# SCH_DONGHO.net
KiCad netlist of a schematic drawn in Altium Designer
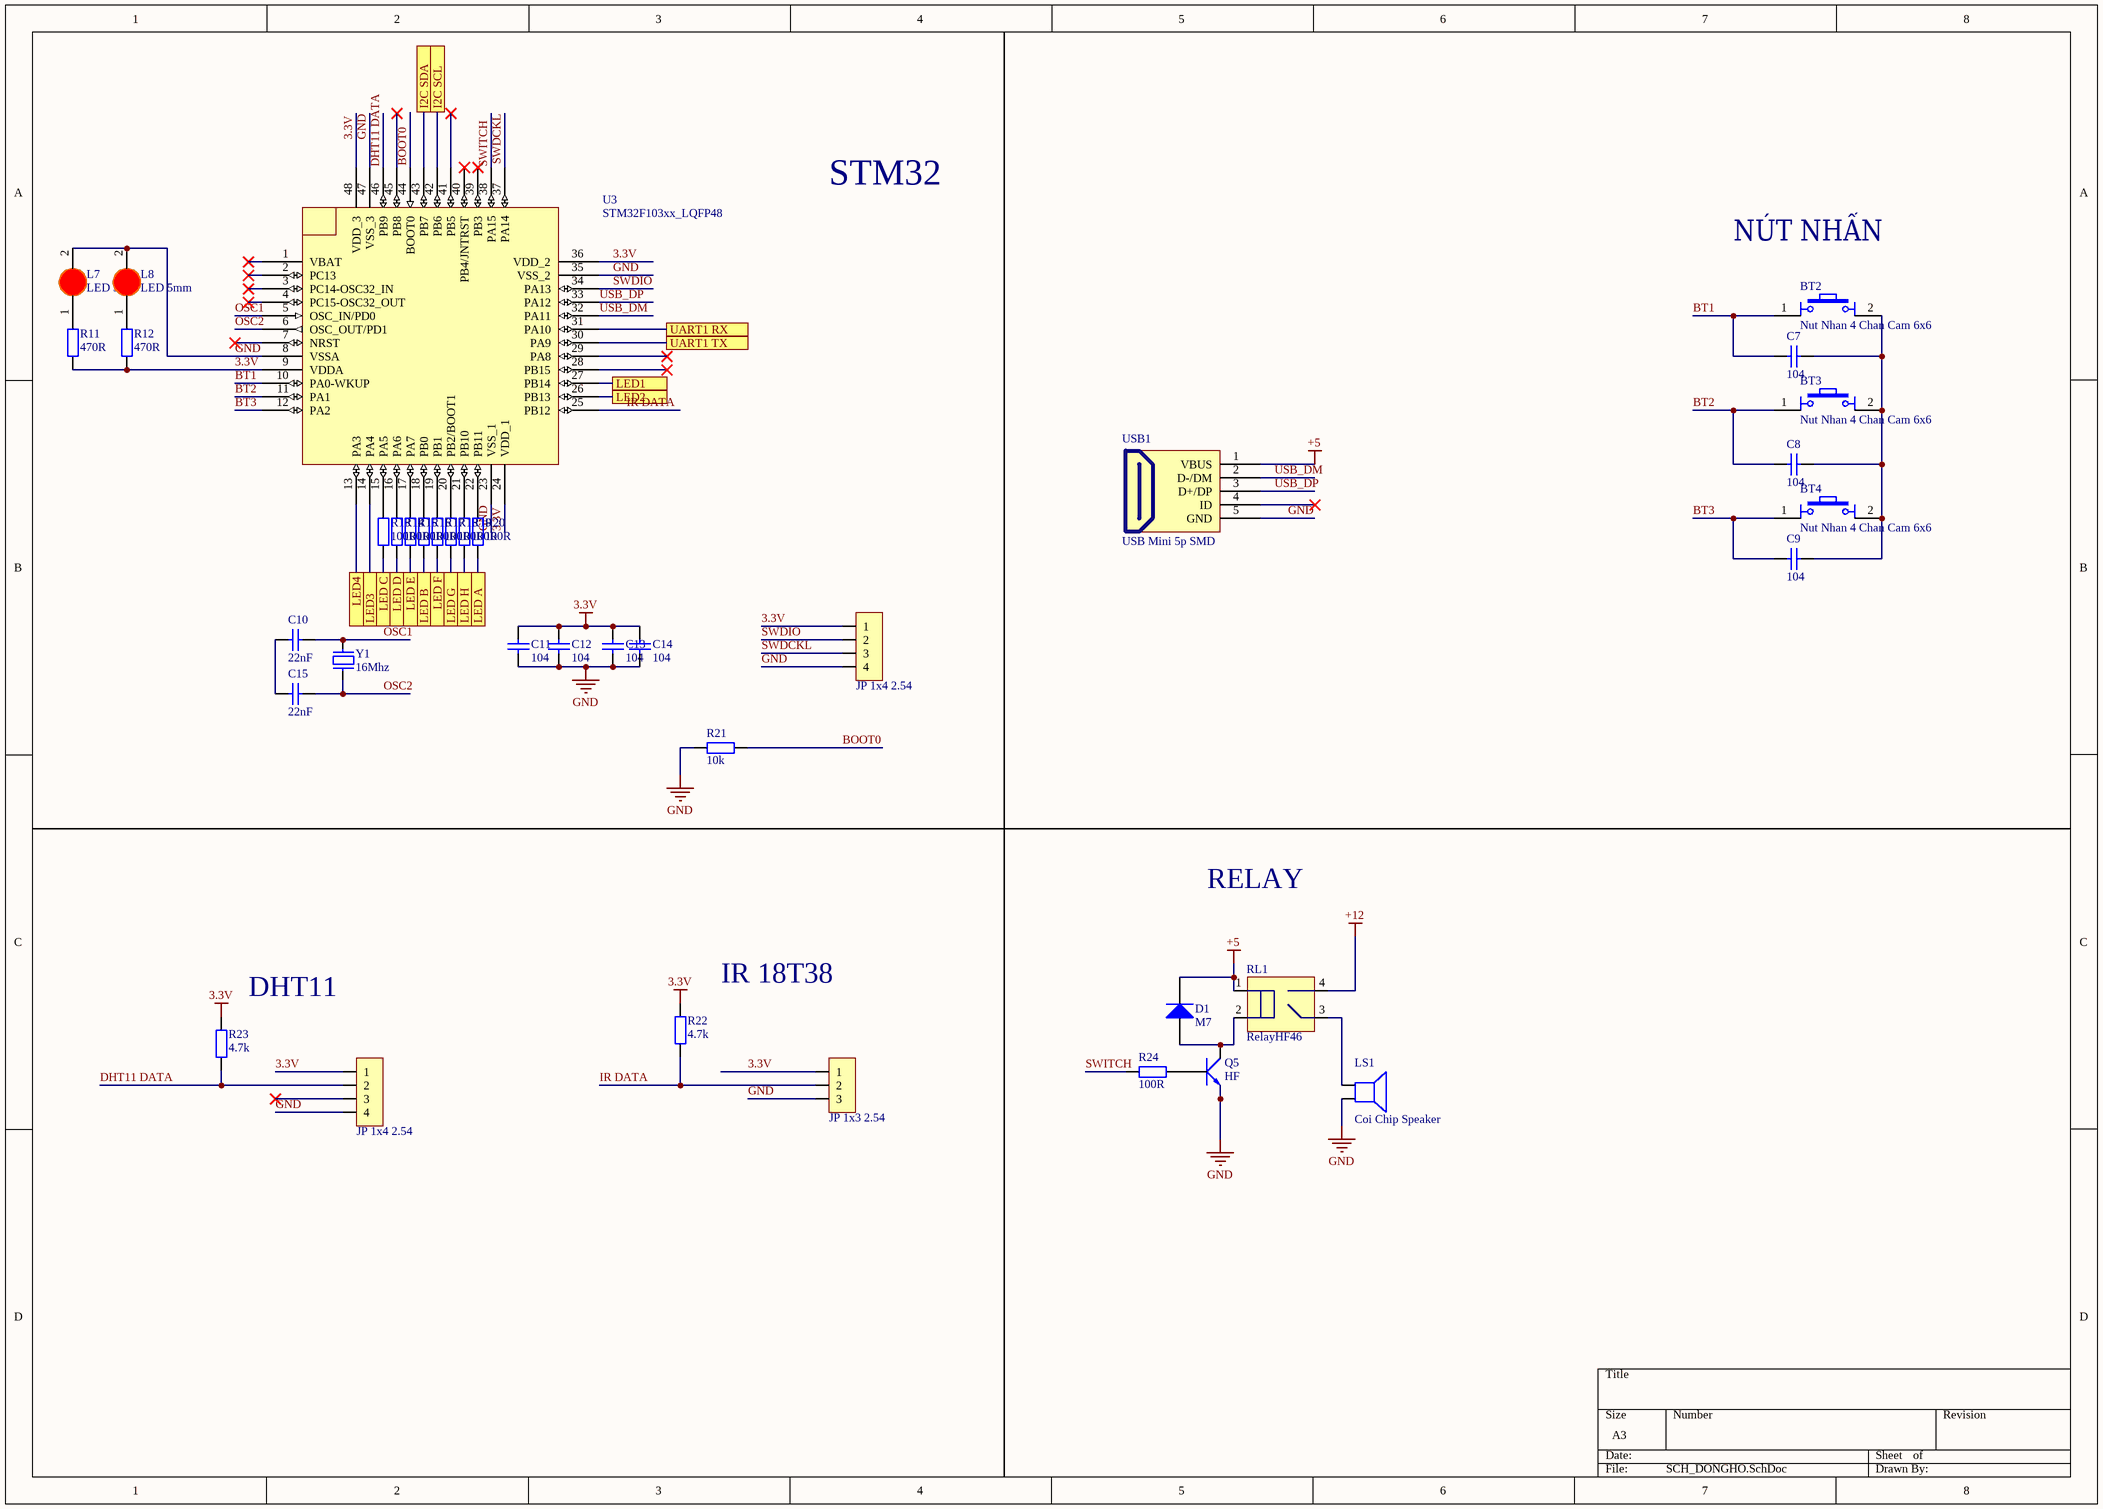
[diagram p0: SCH_DONGHO.SchDoc]

(export (version "E")
  (design (tool "Eeschema 10.0.6"))
  (components
    (comp (ref "BT2")
      (value "Nut Nhan 4 Chan Cam 6x6")
      (footprint "Nut Nhan 4 Chan Cam 6x6")
      (description "Nut Nhan 4 Chan 6x6mm")
      (libsource (lib "Altium_Lib_by_KhueNguyenCreator") (part "Nut Nhan 4 Chan Cam 6x6"))
    )
    (comp (ref "BT3")
      (value "Nut Nhan 4 Chan Cam 6x6")
      (footprint "Nut Nhan 4 Chan Cam 6x6")
      (description "Nut Nhan 4 Chan 6x6mm")
      (libsource (lib "Altium_Lib_by_KhueNguyenCreator") (part "Nut Nhan 4 Chan Cam 6x6"))
    )
    (comp (ref "BT4")
      (value "Nut Nhan 4 Chan Cam 6x6")
      (footprint "Nut Nhan 4 Chan Cam 6x6")
      (description "Nut Nhan 4 Chan 6x6mm")
      (libsource (lib "Altium_Lib_by_KhueNguyenCreator") (part "Nut Nhan 4 Chan Cam 6x6"))
    )
    (comp (ref "C7")
      (value "104")
      (footprint "tu 0805")
      (description "Dán")
      (libsource (lib "Altium_Lib_by_KhueNguyenCreator") (part "Tu 0805 104 50V 10%"))
    )
    (comp (ref "C8")
      (value "104")
      (footprint "tu 0805")
      (description "Dán")
      (libsource (lib "Altium_Lib_by_KhueNguyenCreator") (part "Tu 0805 104 50V 10%"))
    )
    (comp (ref "C9")
      (value "104")
      (footprint "tu 0805")
      (description "Dán")
      (libsource (lib "Altium_Lib_by_KhueNguyenCreator") (part "Tu 0805 104 50V 10%"))
    )
    (comp (ref "C10")
      (value "22nF")
      (footprint "tu 0805")
      (description "Dán")
      (libsource (lib "Altium_Lib_by_KhueNguyenCreator") (part "Tu 0805 22nF 50V 20%"))
    )
    (comp (ref "C11")
      (value "104")
      (footprint "tu 0805")
      (description "Dán")
      (libsource (lib "Altium_Lib_by_KhueNguyenCreator") (part "Tu 0805 104 50V 10%"))
    )
    (comp (ref "C12")
      (value "104")
      (footprint "tu 0805")
      (description "Dán")
      (libsource (lib "Altium_Lib_by_KhueNguyenCreator") (part "Tu 0805 104 50V 10%"))
    )
    (comp (ref "C13")
      (value "104")
      (footprint "tu 0805")
      (description "Dán")
      (libsource (lib "Altium_Lib_by_KhueNguyenCreator") (part "Tu 0805 104 50V 10%"))
    )
    (comp (ref "C14")
      (value "104")
      (footprint "tu 0805")
      (description "Dán")
      (libsource (lib "Altium_Lib_by_KhueNguyenCreator") (part "Tu 0805 104 50V 10%"))
    )
    (comp (ref "C15")
      (value "22nF")
      (footprint "tu 0805")
      (description "Dán")
      (libsource (lib "Altium_Lib_by_KhueNguyenCreator") (part "Tu 0805 22nF 50V 20%"))
    )
    (comp (ref "D1")
      (value "M7")
      (footprint "DIODE SMA")
      (description "Dán")
      (libsource (lib "Altium_Lib_by_KhueNguyenCreator") (part "Diode M7 ( 4007 )"))
    )
    (comp (ref "JP1")
      (value "JP 1x4 2.54")
      (footprint "JP 1x4 CT")
      (description "Cắm")
      (libsource (lib "Altium_Lib_by_KhueNguyenCreator") (part "JP 1x4 2.54 Cai Thang"))
    )
    (comp (ref "JP2")
      (value "JP 1x4 2.54")
      (footprint "JP 1x4 CT")
      (description "Cắm")
      (libsource (lib "Altium_Lib_by_KhueNguyenCreator") (part "JP 1x4 2.54 Cai Thang"))
    )
    (comp (ref "JP3")
      (value "JP 1x3 2.54")
      (footprint "JP 1x3 CT")
      (description "Cắm")
      (libsource (lib "Altium_Lib_by_KhueNguyenCreator") (part "JP 1x3 2.54 Cai Thang"))
    )
    (comp (ref "L7")
      (value "LED 5mm")
      (footprint "LED-5MM-RED")
      (description "Cắm")
      (libsource (lib "Altium_Lib_by_KhueNguyenCreator") (part "LED 5mm Do"))
    )
    (comp (ref "L8")
      (value "LED 5mm")
      (footprint "LED-5MM-RED")
      (description "Cắm")
      (libsource (lib "Altium_Lib_by_KhueNguyenCreator") (part "LED 5mm Do"))
    )
    (comp (ref "LS1")
      (value "Coi Chip Speaker")
      (footprint "Coi Chip Speacker")
      (description "Còi chip")
      (libsource (lib "Altium_Lib_by_KhueNguyenCreator") (part "Coi Chip Speaker"))
    )
    (comp (ref "Q5")
      (value "HF")
      (footprint "SOT23")
      (description "NPN transistor")
      (libsource (lib "Altium_Lib_by_KhueNguyenCreator") (part "C1815 HF SMD"))
    )
    (comp (ref "R11")
      (value "470R")
      (footprint "Tro SMD 0805")
      (description "Dán")
      (libsource (lib "Altium_Lib_by_KhueNguyenCreator") (part "Tro 0805 5% 470R"))
    )
    (comp (ref "R12")
      (value "470R")
      (footprint "Tro SMD 0805")
      (description "Dán")
      (libsource (lib "Altium_Lib_by_KhueNguyenCreator") (part "Tro 0805 5% 470R"))
    )
    (comp (ref "R13")
      (value "100R")
      (footprint "tro smd 0805")
      (description "Dán")
      (libsource (lib "Altium_Lib_by_KhueNguyenCreator") (part "Tro 0805 5% 100R"))
    )
    (comp (ref "R14")
      (value "100R")
      (footprint "tro smd 0805")
      (description "Dán")
      (libsource (lib "Altium_Lib_by_KhueNguyenCreator") (part "Tro 0805 5% 100R"))
    )
    (comp (ref "R15")
      (value "100R")
      (footprint "tro smd 0805")
      (description "Dán")
      (libsource (lib "Altium_Lib_by_KhueNguyenCreator") (part "Tro 0805 5% 100R"))
    )
    (comp (ref "R16")
      (value "100R")
      (footprint "tro smd 0805")
      (description "Dán")
      (libsource (lib "Altium_Lib_by_KhueNguyenCreator") (part "Tro 0805 5% 100R"))
    )
    (comp (ref "R17")
      (value "100R")
      (footprint "tro smd 0805")
      (description "Dán")
      (libsource (lib "Altium_Lib_by_KhueNguyenCreator") (part "Tro 0805 5% 100R"))
    )
    (comp (ref "R18")
      (value "100R")
      (footprint "tro smd 0805")
      (description "Dán")
      (libsource (lib "Altium_Lib_by_KhueNguyenCreator") (part "Tro 0805 5% 100R"))
    )
    (comp (ref "R19")
      (value "100R")
      (footprint "tro smd 0805")
      (description "Dán")
      (libsource (lib "Altium_Lib_by_KhueNguyenCreator") (part "Tro 0805 5% 100R"))
    )
    (comp (ref "R20")
      (value "100R")
      (footprint "tro smd 0805")
      (description "Dán")
      (libsource (lib "Altium_Lib_by_KhueNguyenCreator") (part "Tro 0805 5% 100R"))
    )
    (comp (ref "R21")
      (value "10k")
      (footprint "tro smd 0805")
      (description "Dán")
      (libsource (lib "Altium_Lib_by_KhueNguyenCreator") (part "Tro 0805 5% 10k"))
    )
    (comp (ref "R22")
      (value "4.7k")
      (footprint "tro smd 0805")
      (description "Dán")
      (libsource (lib "Altium_Lib_by_KhueNguyenCreator") (part "Tro 0805 5% 4.7k"))
    )
    (comp (ref "R23")
      (value "4.7k")
      (footprint "tro smd 0805")
      (description "Dán")
      (libsource (lib "Altium_Lib_by_KhueNguyenCreator") (part "Tro 0805 5% 4.7k"))
    )
    (comp (ref "R24")
      (value "100R")
      (footprint "tro smd 0805")
      (description "Dán")
      (libsource (lib "Altium_Lib_by_KhueNguyenCreator") (part "Tro 0805 5% 100R"))
    )
    (comp (ref "RL1")
      (value "RelayHF46")
      (footprint "Relay 4 chan HF46F")
      (description "Relay 4 chan HF46F")
      (libsource (lib "Altium_Lib_by_KhueNguyenCreator") (part "Relay 4 chan HF46F"))
    )
    (comp (ref "U3")
      (value "STM32F103xx_LQFP48")
      (footprint "STM32_LQPF48")
      (fields (field (name "PUBLISHER") "Altium Limited"))
      (libsource (lib "Altium_Lib_by_KhueNguyenCreator") (part "STM32F103xx_LQFP48"))
    )
    (comp (ref "USB1")
      (value "USB Mini 5p SMD")
      (footprint "USB Mini 5p SMD")
      (description "USB Type B")
      (libsource (lib "Altium_Lib_by_KhueNguyenCreator") (part "USB Mini 5p SMD"))
    )
    (comp (ref "Y1")
      (value "16Mhz")
      (footprint "Thach Anh 2 chan SMD")
      (description "Crystal For all Crystal 2pin.")
      (libsource (lib "Altium_Lib_by_KhueNguyenCreator") (part "Thach Anh 2 chan SMD"))
    )
  )
  (nets
    (net (code "1") (name "+5") (class "Default")
      (node (ref "D1") (pin "2") (pinfunction "K_2") (pintype "passive"))
      (node (ref "RL1") (pin "1") (pintype "passive"))
      (node (ref "USB1") (pin "1") (pinfunction "VBUS_1") (pintype "passive"))
    )
    (net (code "2") (name "+12") (class "Default")
      (node (ref "RL1") (pin "4") (pinfunction "AC/DC_4") (pintype "passive"))
    )
    (net (code "3") (name "/BOOT0") (class "Default")
      (node (ref "R21") (pin "1") (pinfunction "1_1") (pintype "passive"))
      (node (ref "U3") (pin "44") (pinfunction "BOOT0_44") (pintype "input"))
    )
    (net (code "4") (name "/BT1") (class "Default")
      (node (ref "BT2") (pin "1") (pintype "passive"))
      (node (ref "C7") (pin "2") (pinfunction "2_2") (pintype "passive"))
      (node (ref "U3") (pin "10") (pinfunction "PA0-WKUP_10") (pintype "bidirectional"))
    )
    (net (code "5") (name "/BT2") (class "Default")
      (node (ref "BT3") (pin "1") (pintype "passive"))
      (node (ref "C8") (pin "2") (pinfunction "2_2") (pintype "passive"))
      (node (ref "U3") (pin "11") (pinfunction "PA1_11") (pintype "bidirectional"))
    )
    (net (code "6") (name "/BT3") (class "Default")
      (node (ref "BT4") (pin "1") (pintype "passive"))
      (node (ref "C9") (pin "2") (pinfunction "2_2") (pintype "passive"))
      (node (ref "U3") (pin "12") (pinfunction "PA2_12") (pintype "bidirectional"))
    )
    (net (code "7") (name "/DHT11 DATA") (class "Default")
      (node (ref "JP2") (pin "2") (pinfunction "2_2") (pintype "passive"))
      (node (ref "R23") (pin "1") (pinfunction "1_1") (pintype "passive"))
      (node (ref "U3") (pin "46") (pinfunction "PB9_46") (pintype "bidirectional"))
    )
    (net (code "8") (name "/I2C SCL") (class "Default")
      (node (ref "U3") (pin "42") (pinfunction "PB6_42") (pintype "bidirectional"))
    )
    (net (code "9") (name "/I2C SDA") (class "Default")
      (node (ref "U3") (pin "43") (pinfunction "PB7_43") (pintype "bidirectional"))
    )
    (net (code "10") (name "/IR DATA") (class "Default")
      (node (ref "JP3") (pin "2") (pinfunction "2_2") (pintype "passive"))
      (node (ref "R22") (pin "1") (pinfunction "1_1") (pintype "passive"))
      (node (ref "U3") (pin "25") (pinfunction "PB12_25") (pintype "bidirectional"))
    )
    (net (code "11") (name "/LED A") (class "Default")
      (node (ref "R20") (pin "2") (pinfunction "2_2") (pintype "passive"))
    )
    (net (code "12") (name "/LED B") (class "Default")
      (node (ref "R16") (pin "2") (pinfunction "2_2") (pintype "passive"))
    )
    (net (code "13") (name "/LED C") (class "Default")
      (node (ref "R13") (pin "1") (pinfunction "1_1") (pintype "passive"))
    )
    (net (code "14") (name "/LED D") (class "Default")
      (node (ref "R14") (pin "1") (pinfunction "1_1") (pintype "passive"))
    )
    (net (code "15") (name "/LED E") (class "Default")
      (node (ref "R15") (pin "1") (pinfunction "1_1") (pintype "passive"))
    )
    (net (code "16") (name "/LED F") (class "Default")
      (node (ref "R17") (pin "1") (pinfunction "1_1") (pintype "passive"))
    )
    (net (code "17") (name "/LED G") (class "Default")
      (node (ref "R18") (pin "2") (pinfunction "2_2") (pintype "passive"))
    )
    (net (code "18") (name "/LED H") (class "Default")
      (node (ref "R19") (pin "2") (pinfunction "2_2") (pintype "passive"))
    )
    (net (code "19") (name "/LED1") (class "Default")
      (node (ref "U3") (pin "27") (pinfunction "PB14_27") (pintype "bidirectional"))
    )
    (net (code "20") (name "/LED2") (class "Default")
      (node (ref "U3") (pin "26") (pinfunction "PB13_26") (pintype "bidirectional"))
    )
    (net (code "21") (name "/LED3") (class "Default")
      (node (ref "U3") (pin "14") (pinfunction "PA4_14") (pintype "bidirectional"))
    )
    (net (code "22") (name "/LED4") (class "Default")
      (node (ref "U3") (pin "13") (pinfunction "PA3_13") (pintype "bidirectional"))
    )
    (net (code "23") (name "/OSC1") (class "Default")
      (node (ref "C10") (pin "1") (pinfunction "1_1") (pintype "passive"))
      (node (ref "U3") (pin "5") (pinfunction "OSC_IN/PD0_5") (pintype "input"))
      (node (ref "Y1") (pin "2") (pinfunction "2_2") (pintype "passive"))
    )
    (net (code "24") (name "/OSC2") (class "Default")
      (node (ref "C15") (pin "1") (pinfunction "1_1") (pintype "passive"))
      (node (ref "U3") (pin "6") (pinfunction "OSC_OUT/PD1_6") (pintype "output"))
      (node (ref "Y1") (pin "1") (pinfunction "1_1") (pintype "passive"))
    )
    (net (code "25") (name "/SWDCKL") (class "Default")
      (node (ref "JP1") (pin "3") (pinfunction "3_3") (pintype "passive"))
      (node (ref "U3") (pin "37") (pinfunction "PA14_37") (pintype "bidirectional"))
    )
    (net (code "26") (name "/SWDIO") (class "Default")
      (node (ref "JP1") (pin "2") (pinfunction "2_2") (pintype "passive"))
      (node (ref "U3") (pin "34") (pinfunction "PA13_34") (pintype "bidirectional"))
    )
    (net (code "27") (name "/SWITCH") (class "Default")
      (node (ref "R24") (pin "1") (pinfunction "1_1") (pintype "passive"))
      (node (ref "U3") (pin "38") (pinfunction "PA15_38") (pintype "bidirectional"))
    )
    (net (code "28") (name "/UART1 RX") (class "Default")
      (node (ref "U3") (pin "31") (pinfunction "PA10_31") (pintype "bidirectional"))
    )
    (net (code "29") (name "/UART1 TX") (class "Default")
      (node (ref "U3") (pin "30") (pinfunction "PA9_30") (pintype "bidirectional"))
    )
    (net (code "30") (name "/USB_DM") (class "Default")
      (node (ref "U3") (pin "32") (pinfunction "PA11_32") (pintype "bidirectional"))
      (node (ref "USB1") (pin "2") (pinfunction "D-/DM_2") (pintype "passive"))
    )
    (net (code "31") (name "/USB_DP") (class "Default")
      (node (ref "U3") (pin "33") (pinfunction "PA12_33") (pintype "bidirectional"))
      (node (ref "USB1") (pin "3") (pinfunction "D+/DP_3") (pintype "passive"))
    )
    (net (code "32") (name "3.3V") (class "Default")
      (node (ref "C11") (pin "1") (pinfunction "1_1") (pintype "passive"))
      (node (ref "C12") (pin "1") (pinfunction "1_1") (pintype "passive"))
      (node (ref "C13") (pin "1") (pinfunction "1_1") (pintype "passive"))
      (node (ref "C14") (pin "1") (pinfunction "1_1") (pintype "passive"))
      (node (ref "JP1") (pin "1") (pinfunction "1_1") (pintype "passive"))
      (node (ref "JP2") (pin "1") (pinfunction "1_1") (pintype "passive"))
      (node (ref "JP3") (pin "1") (pinfunction "1_1") (pintype "passive"))
      (node (ref "R11") (pin "1") (pinfunction "1_1") (pintype "passive"))
      (node (ref "R12") (pin "1") (pinfunction "1_1") (pintype "passive"))
      (node (ref "R22") (pin "2") (pinfunction "2_2") (pintype "passive"))
      (node (ref "R23") (pin "2") (pinfunction "2_2") (pintype "passive"))
      (node (ref "U3") (pin "24") (pinfunction "VDD_1_24") (pintype "power_in"))
      (node (ref "U3") (pin "36") (pinfunction "VDD_2_36") (pintype "power_in"))
      (node (ref "U3") (pin "48") (pinfunction "VDD_3_48") (pintype "power_in"))
      (node (ref "U3") (pin "9") (pinfunction "VDDA_9") (pintype "power_in"))
    )
    (net (code "33") (name "GND") (class "Default")
      (node (ref "C11") (pin "2") (pinfunction "2_2") (pintype "passive"))
      (node (ref "C12") (pin "2") (pinfunction "2_2") (pintype "passive"))
      (node (ref "C13") (pin "2") (pinfunction "2_2") (pintype "passive"))
      (node (ref "C14") (pin "2") (pinfunction "2_2") (pintype "passive"))
      (node (ref "JP1") (pin "4") (pinfunction "4_4") (pintype "passive"))
      (node (ref "JP2") (pin "4") (pinfunction "4_4") (pintype "passive"))
      (node (ref "JP3") (pin "3") (pinfunction "3_3") (pintype "passive"))
      (node (ref "L7") (pin "2") (pinfunction "K_2") (pintype "passive"))
      (node (ref "L8") (pin "2") (pinfunction "K_2") (pintype "passive"))
      (node (ref "LS1") (pin "2") (pinfunction "2_2") (pintype "passive"))
      (node (ref "Q5") (pin "2") (pinfunction "E_2") (pintype "passive"))
      (node (ref "R21") (pin "2") (pinfunction "2_2") (pintype "passive"))
      (node (ref "U3") (pin "23") (pinfunction "VSS_1_23") (pintype "power_in"))
      (node (ref "U3") (pin "35") (pinfunction "VSS_2_35") (pintype "power_in"))
      (node (ref "U3") (pin "47") (pinfunction "VSS_3_47") (pintype "power_in"))
      (node (ref "U3") (pin "8") (pinfunction "VSSA_8") (pintype "power_in"))
      (node (ref "USB1") (pin "5") (pinfunction "GND_5") (pintype "passive"))
    )
    (net (code "34") (name "Net-(BT2-Pad2)") (class "Default")
      (node (ref "BT2") (pin "2") (pintype "passive"))
      (node (ref "BT3") (pin "2") (pintype "passive"))
      (node (ref "BT4") (pin "2") (pintype "passive"))
      (node (ref "C7") (pin "1") (pinfunction "1_1") (pintype "passive"))
      (node (ref "C8") (pin "1") (pinfunction "1_1") (pintype "passive"))
      (node (ref "C9") (pin "1") (pinfunction "1_1") (pintype "passive"))
    )
    (net (code "35") (name "Net-(C10-Pad2)") (class "Default")
      (node (ref "C10") (pin "2") (pinfunction "2_2") (pintype "passive"))
      (node (ref "C15") (pin "2") (pinfunction "2_2") (pintype "passive"))
    )
    (net (code "36") (name "Net-(D1-A)") (class "Default")
      (node (ref "D1") (pin "1") (pinfunction "A_1") (pintype "passive"))
      (node (ref "Q5") (pin "3") (pinfunction "C_3") (pintype "passive"))
      (node (ref "RL1") (pin "2") (pintype "passive"))
    )
    (net (code "37") (name "Net-(L7-A)") (class "Default")
      (node (ref "L7") (pin "1") (pinfunction "A_1") (pintype "passive"))
      (node (ref "R11") (pin "2") (pinfunction "2_2") (pintype "passive"))
    )
    (net (code "38") (name "Net-(L8-A)") (class "Default")
      (node (ref "L8") (pin "1") (pinfunction "A_1") (pintype "passive"))
      (node (ref "R12") (pin "2") (pinfunction "2_2") (pintype "passive"))
    )
    (net (code "39") (name "Net-(LS1-Pad1)") (class "Default")
      (node (ref "LS1") (pin "1") (pinfunction "1_1") (pintype "passive"))
      (node (ref "RL1") (pin "3") (pinfunction "AC/DC_3") (pintype "passive"))
    )
    (net (code "40") (name "Net-(Q5-B)") (class "Default")
      (node (ref "Q5") (pin "1") (pinfunction "B_1") (pintype "passive"))
      (node (ref "R24") (pin "2") (pinfunction "2_2") (pintype "passive"))
    )
    (net (code "41") (name "Net-(U3-PA5)") (class "Default")
      (node (ref "R13") (pin "2") (pinfunction "2_2") (pintype "passive"))
      (node (ref "U3") (pin "15") (pinfunction "PA5_15") (pintype "bidirectional"))
    )
    (net (code "42") (name "Net-(U3-PA6)") (class "Default")
      (node (ref "R14") (pin "2") (pinfunction "2_2") (pintype "passive"))
      (node (ref "U3") (pin "16") (pinfunction "PA6_16") (pintype "bidirectional"))
    )
    (net (code "43") (name "Net-(U3-PA7)") (class "Default")
      (node (ref "R15") (pin "2") (pinfunction "2_2") (pintype "passive"))
      (node (ref "U3") (pin "17") (pinfunction "PA7_17") (pintype "bidirectional"))
    )
    (net (code "44") (name "Net-(U3-PB0)") (class "Default")
      (node (ref "R16") (pin "1") (pinfunction "1_1") (pintype "passive"))
      (node (ref "U3") (pin "18") (pinfunction "PB0_18") (pintype "bidirectional"))
    )
    (net (code "45") (name "Net-(U3-PB1)") (class "Default")
      (node (ref "R17") (pin "2") (pinfunction "2_2") (pintype "passive"))
      (node (ref "U3") (pin "19") (pinfunction "PB1_19") (pintype "bidirectional"))
    )
    (net (code "46") (name "Net-(U3-PB2{slash}BOOT1)") (class "Default")
      (node (ref "R18") (pin "1") (pinfunction "1_1") (pintype "passive"))
      (node (ref "U3") (pin "20") (pinfunction "PB2/BOOT1_20") (pintype "bidirectional"))
    )
    (net (code "47") (name "Net-(U3-PB10)") (class "Default")
      (node (ref "R19") (pin "1") (pinfunction "1_1") (pintype "passive"))
      (node (ref "U3") (pin "21") (pinfunction "PB10_21") (pintype "bidirectional"))
    )
    (net (code "48") (name "Net-(U3-PB11)") (class "Default")
      (node (ref "R20") (pin "1") (pinfunction "1_1") (pintype "passive"))
      (node (ref "U3") (pin "22") (pinfunction "PB11_22") (pintype "bidirectional"))
    )
    (net (code "49") (name "unconnected-(JP2-Pad3)") (class "Default")
      (node (ref "JP2") (pin "3") (pinfunction "3_3") (pintype "passive+no_connect"))
    )
    (net (code "50") (name "unconnected-(U3-NRST-Pad7)") (class "Default")
      (node (ref "U3") (pin "7") (pinfunction "NRST_7") (pintype "bidirectional+no_connect"))
    )
    (net (code "51") (name "unconnected-(U3-PA8-Pad29)") (class "Default")
      (node (ref "U3") (pin "29") (pinfunction "PA8_29") (pintype "bidirectional+no_connect"))
    )
    (net (code "52") (name "unconnected-(U3-PB3-Pad39)") (class "Default")
      (node (ref "U3") (pin "39") (pinfunction "PB3_39") (pintype "bidirectional+no_connect"))
    )
    (net (code "53") (name "unconnected-(U3-PB4{slash}JNTRST-Pad40)") (class "Default")
      (node (ref "U3") (pin "40") (pinfunction "PB4/JNTRST_40") (pintype "bidirectional+no_connect"))
    )
    (net (code "54") (name "unconnected-(U3-PB5-Pad41)") (class "Default")
      (node (ref "U3") (pin "41") (pinfunction "PB5_41") (pintype "bidirectional+no_connect"))
    )
    (net (code "55") (name "unconnected-(U3-PB8-Pad45)") (class "Default")
      (node (ref "U3") (pin "45") (pinfunction "PB8_45") (pintype "bidirectional+no_connect"))
    )
    (net (code "56") (name "unconnected-(U3-PB15-Pad28)") (class "Default")
      (node (ref "U3") (pin "28") (pinfunction "PB15_28") (pintype "bidirectional+no_connect"))
    )
    (net (code "57") (name "unconnected-(U3-PC13-Pad2)") (class "Default")
      (node (ref "U3") (pin "2") (pinfunction "PC13_2") (pintype "bidirectional+no_connect"))
    )
    (net (code "58") (name "unconnected-(U3-PC14-OSC32_IN-Pad3)") (class "Default")
      (node (ref "U3") (pin "3") (pinfunction "PC14-OSC32_IN_3") (pintype "bidirectional+no_connect"))
    )
    (net (code "59") (name "unconnected-(U3-PC15-OSC32_OUT-Pad4)") (class "Default")
      (node (ref "U3") (pin "4") (pinfunction "PC15-OSC32_OUT_4") (pintype "bidirectional+no_connect"))
    )
    (net (code "60") (name "unconnected-(U3-VBAT-Pad1)") (class "Default")
      (node (ref "U3") (pin "1") (pinfunction "VBAT_1") (pintype "power_in+no_connect"))
    )
    (net (code "61") (name "unconnected-(USB1-ID-Pad4)") (class "Default")
      (node (ref "USB1") (pin "4") (pinfunction "ID_4") (pintype "passive+no_connect"))
    )
  )
)
